# JCM800-2204.net
KiCad netlist of a schematic drawn in Altium Designer
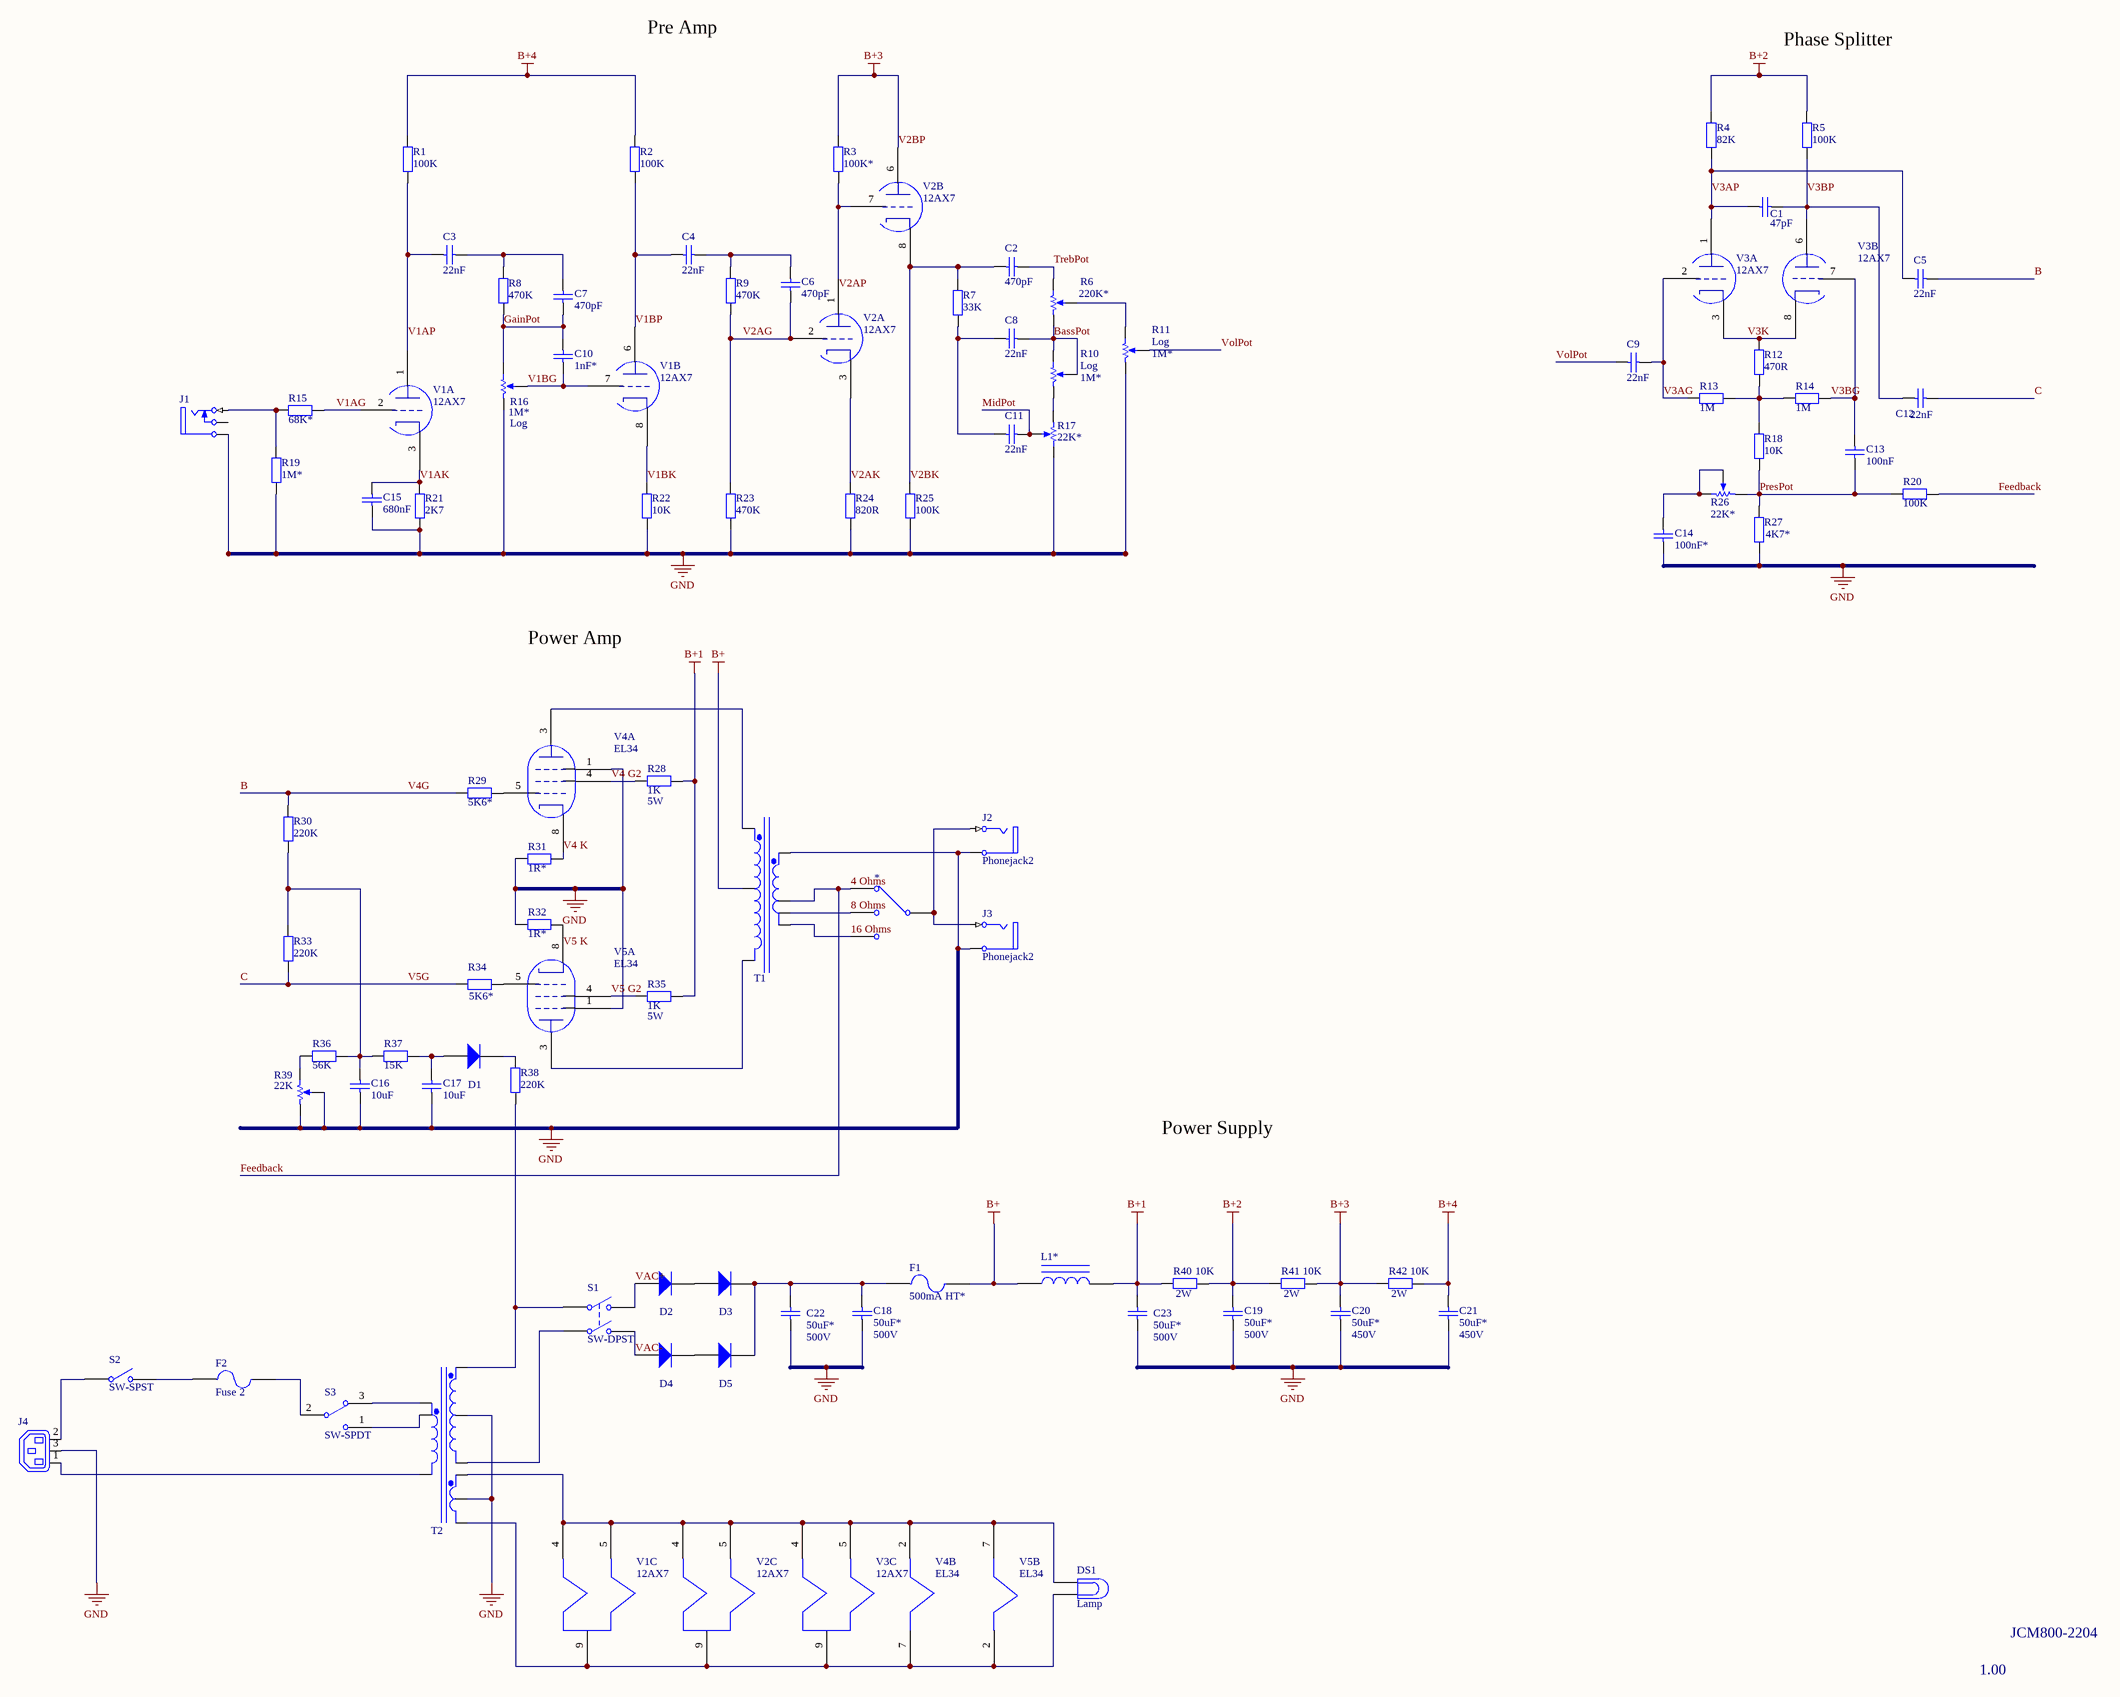
[diagram p0: JCM800-2204.SchDoc]

(export (version "E")
  (design (tool "Eeschema 10.0.6"))
  (components
    (comp (ref "*") (value "Switch 3way") (libsource (lib "RAKS") (part "Switch 3way")))
    (comp (ref "C1")
      (value "47pF")
      (footprint "3CM TURRET")
      (description "Capacitor, ceramic, RSV, 50V, 0805")
      (fields
        (field (name "PART NUMBER") "RK-cer-RSV-50V-0805")
        (field (name "Comment") "Cap-cer-RSV-50V-0805")
      )
      (libsource (lib "RAKS") (part "Cap-cer-RSV-50V-0805"))
    )
    (comp (ref "C2")
      (value "470pF")
      (footprint "6cm Turret")
      (description "Capacitor, ceramic, RSV, 50V, 0805")
      (fields
        (field (name "PART NUMBER") "RK-cer-RSV-50V-0805")
        (field (name "Comment") "Cap-cer-RSV-50V-0805")
      )
      (libsource (lib "RAKS") (part "Cap-cer-RSV-50V-0805"))
    )
    (comp (ref "C3")
      (value "22nF")
      (footprint "3CM TURRET")
      (description "Capacitor, ceramic, RSV, 50V, 0805")
      (fields
        (field (name "PART NUMBER") "RK-cer-RSV-50V-0805")
        (field (name "Comment") "Cap-cer-RSV-50V-0805")
      )
      (libsource (lib "RAKS") (part "Cap-cer-RSV-50V-0805"))
    )
    (comp (ref "C4")
      (value "22nF")
      (footprint "3CM TURRET")
      (description "Capacitor, ceramic, RSV, 50V, 0805")
      (fields
        (field (name "PART NUMBER") "RK-cer-RSV-50V-0805")
        (field (name "Comment") "Cap-cer-RSV-50V-0805")
      )
      (libsource (lib "RAKS") (part "Cap-cer-RSV-50V-0805"))
    )
    (comp (ref "C5")
      (value "22nF")
      (footprint "6CM TURRET")
      (description "Capacitor, ceramic, RSV, 50V, 0805")
      (fields
        (field (name "PART NUMBER") "RK-cer-RSV-50V-0805")
        (field (name "Comment") "Cap-cer-RSV-50V-0805")
      )
      (libsource (lib "RAKS") (part "Cap-cer-RSV-50V-0805"))
    )
    (comp (ref "C6")
      (value "470pF")
      (description "Capacitor, ceramic, RSV, 50V, 0805")
      (fields
        (field (name "PART NUMBER") "RK-cer-RSV-50V-0805")
        (field (name "Comment") "Cap-cer-RSV-50V-0805")
      )
      (libsource (lib "RAKS") (part "Cap-cer-RSV-50V-0805"))
    )
    (comp (ref "C7")
      (value "470pF")
      (description "Capacitor, ceramic, RSV, 50V, 0805")
      (fields
        (field (name "PART NUMBER") "RK-cer-RSV-50V-0805")
        (field (name "Comment") "Cap-cer-RSV-50V-0805")
      )
      (libsource (lib "RAKS") (part "Cap-cer-RSV-50V-0805"))
    )
    (comp (ref "C8")
      (value "22nF")
      (footprint "6cm Turret")
      (description "Capacitor, ceramic, RSV, 50V, 0805")
      (fields
        (field (name "PART NUMBER") "RK-cer-RSV-50V-0805")
        (field (name "Comment") "Cap-cer-RSV-50V-0805")
      )
      (libsource (lib "RAKS") (part "Cap-cer-RSV-50V-0805"))
    )
    (comp (ref "C9")
      (value "22nF")
      (footprint "6cm Turret")
      (description "Capacitor, ceramic, RSV, 50V, 0805")
      (fields
        (field (name "PART NUMBER") "RK-cer-RSV-50V-0805")
        (field (name "Comment") "Cap-cer-RSV-50V-0805")
      )
      (libsource (lib "RAKS") (part "Cap-cer-RSV-50V-0805"))
    )
    (comp (ref "C10")
      (value "1nF*")
      (description "Capacitor, ceramic, RSV, 50V, 0805")
      (fields
        (field (name "PART NUMBER") "RK-cer-RSV-50V-0805")
        (field (name "Comment") "Cap-cer-RSV-50V-0805")
      )
      (libsource (lib "RAKS") (part "Cap-cer-RSV-50V-0805"))
    )
    (comp (ref "C11")
      (value "22nF")
      (footprint "6cm Turret")
      (description "Capacitor, ceramic, RSV, 50V, 0805")
      (fields
        (field (name "PART NUMBER") "RK-cer-RSV-50V-0805")
        (field (name "Comment") "Cap-cer-RSV-50V-0805")
      )
      (libsource (lib "RAKS") (part "Cap-cer-RSV-50V-0805"))
    )
    (comp (ref "C12")
      (value "22nF")
      (footprint "6CM TURRET")
      (description "Capacitor, ceramic, RSV, 50V, 0805")
      (fields
        (field (name "PART NUMBER") "RK-cer-RSV-50V-0805")
        (field (name "Comment") "Cap-cer-RSV-50V-0805")
      )
      (libsource (lib "RAKS") (part "Cap-cer-RSV-50V-0805"))
    )
    (comp (ref "C13")
      (value "100nF")
      (footprint "6CM TURRET")
      (description "Capacitor, ceramic, RSV, 50V, 0805")
      (fields
        (field (name "PART NUMBER") "RK-cer-RSV-50V-0805")
        (field (name "Comment") "Cap-cer-RSV-50V-0805")
      )
      (libsource (lib "RAKS") (part "Cap-cer-RSV-50V-0805"))
    )
    (comp (ref "C14")
      (value "100nF*")
      (description "Capacitor, ceramic, RSV, 50V, 0805")
      (fields
        (field (name "PART NUMBER") "RK-cer-RSV-50V-0805")
        (field (name "Comment") "Cap-cer-RSV-50V-0805")
      )
      (libsource (lib "RAKS") (part "Cap-cer-RSV-50V-0805"))
    )
    (comp (ref "C15")
      (value "680nF")
      (description "Capacitor, ceramic, RSV, 50V, 0805")
      (fields
        (field (name "PART NUMBER") "RK-cer-RSV-50V-0805")
        (field (name "Comment") "Cap-cer-RSV-50V-0805")
      )
      (libsource (lib "RAKS") (part "Cap-cer-RSV-50V-0805"))
    )
    (comp (ref "C16")
      (value "10uF")
      (footprint "6CM TURRET")
      (description "Capacitor, ceramic, RSV, 50V, 0805")
      (fields
        (field (name "PART NUMBER") "RK-cer-RSV-50V-0805")
        (field (name "Comment") "Cap-cer-RSV-50V-0805")
      )
      (libsource (lib "RAKS") (part "Cap-cer-RSV-50V-0805"))
    )
    (comp (ref "C17")
      (value "10uF")
      (footprint "6CM TURRET")
      (description "Capacitor, ceramic, RSV, 50V, 0805")
      (fields
        (field (name "PART NUMBER") "RK-cer-RSV-50V-0805")
        (field (name "Comment") "Cap-cer-RSV-50V-0805")
      )
      (libsource (lib "RAKS") (part "Cap-cer-RSV-50V-0805"))
    )
    (comp (ref "C18")
      (value "50uF*")
      (footprint "6cm Turret")
      (description "Capacitor, ceramic, RSV, 50V, 0805")
      (fields
        (field (name "PART NUMBER") "RK-cer-RSV-50V-0805")
        (field (name "VOLTAGE") "500V")
        (field (name "Comment") "Cap-cer-RSV-50V-0805")
      )
      (libsource (lib "RAKS") (part "Cap-cer-RSV-50V-0805"))
    )
    (comp (ref "C19")
      (value "50uF*")
      (footprint "6cm Turret")
      (description "Capacitor, ceramic, RSV, 50V, 0805")
      (fields
        (field (name "PART NUMBER") "RK-cer-RSV-50V-0805")
        (field (name "VOLTAGE") "500V")
        (field (name "Comment") "Cap-cer-RSV-50V-0805")
      )
      (libsource (lib "RAKS") (part "Cap-cer-RSV-50V-0805"))
    )
    (comp (ref "C20")
      (value "50uF*")
      (footprint "6cm Turret")
      (description "Capacitor, ceramic, RSV, 50V, 0805")
      (fields
        (field (name "PART NUMBER") "RK-cer-RSV-50V-0805")
        (field (name "VOLTAGE") "450V")
        (field (name "Comment") "Cap-cer-RSV-50V-0805")
      )
      (libsource (lib "RAKS") (part "Cap-cer-RSV-50V-0805"))
    )
    (comp (ref "C21")
      (value "50uF*")
      (footprint "6cm Turret")
      (description "Capacitor, ceramic, RSV, 50V, 0805")
      (fields
        (field (name "PART NUMBER") "RK-cer-RSV-50V-0805")
        (field (name "VOLTAGE") "450V")
        (field (name "Comment") "Cap-cer-RSV-50V-0805")
      )
      (libsource (lib "RAKS") (part "Cap-cer-RSV-50V-0805"))
    )
    (comp (ref "C22")
      (value "50uF*")
      (description "Capacitor, ceramic, RSV, 50V, 0805")
      (fields
        (field (name "PART NUMBER") "RK-cer-RSV-50V-0805")
        (field (name "VOLTAGE") "500V")
        (field (name "Comment") "Cap-cer-RSV-50V-0805")
      )
      (libsource (lib "RAKS") (part "Cap-cer-RSV-50V-0805"))
    )
    (comp (ref "C23")
      (value "50uF*")
      (footprint "6cm Turret")
      (description "Capacitor, ceramic, RSV, 50V, 0805")
      (fields
        (field (name "PART NUMBER") "RK-cer-RSV-50V-0805")
        (field (name "VOLTAGE") "500V")
        (field (name "Comment") "Cap-cer-RSV-50V-0805")
      )
      (libsource (lib "RAKS") (part "Cap-cer-RSV-50V-0805"))
    )
    (comp (ref "D1")
      (value "1N4148")
      (footprint "3cm Turret")
      (description "Diode")
      (fields (field (name "PART NUMBER") "RK-Diode-1N4148"))
      (libsource (lib "RAKS") (part "Diode-1N4148"))
    )
    (comp (ref "D2")
      (value "1N4148")
      (footprint "3cm Turret")
      (description "Diode")
      (fields (field (name "PART NUMBER") "RK-Diode-1N4148"))
      (libsource (lib "RAKS") (part "Diode-1N4148"))
    )
    (comp (ref "D3")
      (value "1N4148")
      (footprint "3cm Turret")
      (description "Diode")
      (fields (field (name "PART NUMBER") "RK-Diode-1N4148"))
      (libsource (lib "RAKS") (part "Diode-1N4148"))
    )
    (comp (ref "D4")
      (value "1N4148")
      (footprint "3cm Turret")
      (description "Diode")
      (fields (field (name "PART NUMBER") "RK-Diode-1N4148"))
      (libsource (lib "RAKS") (part "Diode-1N4148"))
    )
    (comp (ref "D5")
      (value "1N4148")
      (footprint "3cm Turret")
      (description "Diode")
      (fields (field (name "PART NUMBER") "RK-Diode-1N4148"))
      (libsource (lib "RAKS") (part "Diode-1N4148"))
    )
    (comp (ref "DS1")
      (value "Lamp")
      (description "Incandescent Bulb")
      (fields (field (name "PUBLISHER") "Altium Limited"))
      (libsource (lib "Miscellaneous Devices") (part "Lamp"))
    )
    (comp (ref "F1")
      (value "500mA HT*")
      (description "Fuse")
      (fields (field (name "PUBLISHER") "Altium Limited"))
      (libsource (lib "Miscellaneous Devices") (part "Fuse 2"))
    )
    (comp (ref "F2")
      (value "Fuse 2")
      (description "Fuse")
      (fields (field (name "PUBLISHER") "Altium Limited"))
      (libsource (lib "Miscellaneous Devices") (part "Fuse 2"))
    )
    (comp (ref "J1")
      (value "Phonejack2 TN")
      (footprint "JACK/6-V3A")
      (description "Jack Socket, 1/4\" [6.5mm], Thru-Hole, Vertical, 2-Conductor with Tip closed")
      (fields (field (name "PUBLISHER") "Altium Limited"))
      (libsource (lib "Miscellaneous Connectors") (part "Phonejack2 TN"))
    )
    (comp (ref "J2")
      (value "Phonejack2")
      (footprint "JACK/6-V2")
      (description "Jack Socket, 1/4\" [6.5mm], Thru-Hole, Vertical, 2-Conductor Open Circuit")
      (fields (field (name "PUBLISHER") "Altium Limited"))
      (libsource (lib "Miscellaneous Connectors") (part "Phonejack2"))
    )
    (comp (ref "J3")
      (value "Phonejack2")
      (footprint "JACK/6-V2")
      (description "Jack Socket, 1/4\" [6.5mm], Thru-Hole, Vertical, 2-Conductor Open Circuit")
      (fields (field (name "PUBLISHER") "Altium Limited"))
      (libsource (lib "Miscellaneous Connectors") (part "Phonejack2"))
    )
    (comp (ref "J4")
      (value "Plug AC Female")
      (description "IEC Mains Power Outlet, EN60 320-2-2 F Class I, PC Flange Rear Mount, Chassis Socket")
      (fields (field (name "PUBLISHER") "Altium Limited"))
      (libsource (lib "Miscellaneous Connectors") (part "Plug AC Female"))
    )
    (comp (ref "L1*")
      (value "Inductor Iron")
      (description "Magnetic-Core Inductor")
      (fields (field (name "PUBLISHER") "Altium Limited"))
      (libsource (lib "Miscellaneous Devices") (part "Inductor Iron"))
    )
    (comp (ref "R1")
      (value "100K")
      (footprint "3CM TURRET")
      (description "Resistor, 100K, 0805, 1%, 1/8W")
      (fields
        (field (name "PART NUMBER") "RK-100K-0805-1%-1/8W")
        (field (name "Comment") "Res-100K-0805-1%-1/8W")
      )
      (libsource (lib "RAKS") (part "Res-100K-0805-1%-1/8W"))
    )
    (comp (ref "R2")
      (value "100K")
      (footprint "3CM TURRET")
      (description "Resistor, 100K, 0805, 1%, 1/8W")
      (fields
        (field (name "PART NUMBER") "RK-100K-0805-1%-1/8W")
        (field (name "Comment") "Res-100K-0805-1%-1/8W")
      )
      (libsource (lib "RAKS") (part "Res-100K-0805-1%-1/8W"))
    )
    (comp (ref "R3")
      (value "100K*")
      (description "Resistor, 100K, 0805, 1%, 1/8W")
      (fields
        (field (name "PART NUMBER") "RK-100K-0805-1%-1/8W")
        (field (name "Comment") "Res-100K-0805-1%-1/8W")
      )
      (libsource (lib "RAKS") (part "Res-100K-0805-1%-1/8W"))
    )
    (comp (ref "R4")
      (value "82K")
      (footprint "3CM TURRET")
      (description "Resistor, 82K, 0805, 1%, 1/8W")
      (fields
        (field (name "PART NUMBER") "RK-82K-0805-1%-1/8W")
        (field (name "Comment") "Res-82K-0805-1%-1/8W")
      )
      (libsource (lib "RAKS") (part "Res-82K-0805-1%-1/8W"))
    )
    (comp (ref "R5")
      (value "100K")
      (footprint "3CM TURRET")
      (description "Resistor, 100K, 0805, 1%, 1/8W")
      (fields
        (field (name "PART NUMBER") "RK-100K-0805-1%-1/8W")
        (field (name "Comment") "Res-100K-0805-1%-1/8W")
      )
      (libsource (lib "RAKS") (part "Res-100K-0805-1%-1/8W"))
    )
    (comp (ref "R6")
      (value "220K*")
      (description "Potentiometer")
      (fields (field (name "Comment") "RPot") (field (name "PUBLISHER") "Altium Limited"))
      (libsource (lib "Miscellaneous Devices") (part "RPot"))
    )
    (comp (ref "R7")
      (value "33K")
      (footprint "3CM TURRET")
      (description "Resistor, 33K, 0805, 1%, 1/8W")
      (fields
        (field (name "PART NUMBER") "RK-33K-0805-1%-1/8W")
        (field (name "Comment") "Res-33K-0805-1%-1/8W")
      )
      (libsource (lib "RAKS") (part "Res-33K-0805-1%-1/8W"))
    )
    (comp (ref "R8")
      (value "470K")
      (footprint "3CM TURRET")
      (description "Resistor, 470K, 0805, 1%, 1/8W")
      (fields
        (field (name "PART NUMBER") "RK-470K-0805-1%-1/8W")
        (field (name "Comment") "Res-470K-0805-1%-1/8W")
      )
      (libsource (lib "RAKS") (part "Res-470K-0805-1%-1/8W"))
    )
    (comp (ref "R9")
      (value "470K")
      (footprint "6CM TURRET")
      (description "Resistor, 470K, 0805, 1%, 1/8W")
      (fields
        (field (name "PART NUMBER") "RK-470K-0805-1%-1/8W")
        (field (name "Comment") "Res-470K-0805-1%-1/8W")
      )
      (libsource (lib "RAKS") (part "Res-470K-0805-1%-1/8W"))
    )
    (comp (ref "R10")
      (value "Log")
      (description "Potentiometer")
      (fields (field (name "ALTIUM_VALUE") "1M*") (field (name "PUBLISHER") "Altium Limited"))
      (libsource (lib "Miscellaneous Devices") (part "RPot"))
    )
    (comp (ref "R11")
      (value "Log")
      (description "Potentiometer")
      (fields (field (name "ALTIUM_VALUE") "1M*") (field (name "PUBLISHER") "Altium Limited"))
      (libsource (lib "Miscellaneous Devices") (part "RPot"))
    )
    (comp (ref "R12")
      (value "470R")
      (footprint "3CM TURRET")
      (description "Resistor, RSV, 0805, 1%, 1/8W")
      (fields
        (field (name "PART NUMBER") "RK-RSV-0805-1%-1/8W")
        (field (name "Comment") "Res-RSV-0805-1%-1/8W")
      )
      (libsource (lib "") (part "Res-RSV-0805-1%-1/8W_1"))
    )
    (comp (ref "R13")
      (value "1M")
      (footprint "3CM TURRET")
      (description "Resistor, 1M, 0805, 1%, 1/8W")
      (fields
        (field (name "PART NUMBER") "RK-1M-0805-1%-1/8W")
        (field (name "Comment") "Res-1M-0805-1%-1/8W")
      )
      (libsource (lib "RAKS") (part "Res-1M-0805-1%-1/8W"))
    )
    (comp (ref "R14")
      (value "1M")
      (footprint "3CM TURRET")
      (description "Resistor, 1M, 0805, 1%, 1/8W")
      (fields
        (field (name "PART NUMBER") "RK-1M-0805-1%-1/8W")
        (field (name "Comment") "Res-1M-0805-1%-1/8W")
      )
      (libsource (lib "RAKS") (part "Res-1M-0805-1%-1/8W"))
    )
    (comp (ref "R15")
      (value "68K*")
      (description "Resistor, 68K, 0805, 1%, 1/8W")
      (fields
        (field (name "PART NUMBER") "RK-68K-0805-1%-1/8W")
        (field (name "Comment") "Res-68K-0805-1%-1/8W")
      )
      (libsource (lib "RAKS") (part "Res-68K-0805-1%-1/8W"))
    )
    (comp (ref "R16")
      (value "Log")
      (description "Potentiometer")
      (fields (field (name "ALTIUM_VALUE") "1M*") (field (name "PUBLISHER") "Altium Limited"))
      (libsource (lib "Miscellaneous Devices") (part "RPot"))
    )
    (comp (ref "R17")
      (value "22K*")
      (description "Potentiometer")
      (fields (field (name "Comment") "RPot") (field (name "PUBLISHER") "Altium Limited"))
      (libsource (lib "Miscellaneous Devices") (part "RPot"))
    )
    (comp (ref "R18")
      (value "10K")
      (footprint "3CM TURRET")
      (description "Resistor, 10K, 0805, 1%, 1/8W")
      (fields
        (field (name "PART NUMBER") "RK-10K-0805-1%-1/8W")
        (field (name "Comment") "Res-10K-0805-1%-1/8W")
      )
      (libsource (lib "RAKS") (part "Res-10K-0805-1%-1/8W"))
    )
    (comp (ref "R19")
      (value "1M*")
      (description "Resistor, 1M, 0805, 1%, 1/8W")
      (fields
        (field (name "PART NUMBER") "RK-1M-0805-1%-1/8W")
        (field (name "Comment") "Res-1M-0805-1%-1/8W")
      )
      (libsource (lib "") (part "Res-1M-0805-1%-1/8W_1"))
    )
    (comp (ref "R20")
      (value "100K")
      (footprint "6CM TURRET")
      (description "Resistor, 100K, 0805, 1%, 1/8W")
      (fields
        (field (name "PART NUMBER") "RK-100K-0805-1%-1/8W")
        (field (name "Comment") "Res-100K-0805-1%-1/8W")
      )
      (libsource (lib "") (part "Res-100K-0805-1%-1/8W_1"))
    )
    (comp (ref "R21")
      (value "2K7")
      (footprint "6CM TURRET")
      (description "Resistor, 2K7, 0805, 1%, 1/8W")
      (fields
        (field (name "PART NUMBER") "RK-2K7-0805-1%-1/8W")
        (field (name "Comment") "Res-2K7-0805-1%-1/8W")
      )
      (libsource (lib "RAKS") (part "Res-2K7-0805-1%-1/8W"))
    )
    (comp (ref "R22")
      (value "10K")
      (footprint "6CM TURRET")
      (description "Resistor, 10K, 0805, 1%, 1/8W")
      (fields
        (field (name "PART NUMBER") "RK-10K-0805-1%-1/8W")
        (field (name "Comment") "Res-10K-0805-1%-1/8W")
      )
      (libsource (lib "RAKS") (part "Res-10K-0805-1%-1/8W"))
    )
    (comp (ref "R23")
      (value "470K")
      (footprint "6CM TURRET")
      (description "Resistor, 470K, 0805, 1%, 1/8W")
      (fields
        (field (name "PART NUMBER") "RK-470K-0805-1%-1/8W")
        (field (name "Comment") "Res-470K-0805-1%-1/8W")
      )
      (libsource (lib "RAKS") (part "Res-470K-0805-1%-1/8W"))
    )
    (comp (ref "R24")
      (value "820R")
      (footprint "6CM TURRET")
      (description "Resistor, 820R, 0805, 1%, 1/8W")
      (fields
        (field (name "PART NUMBER") "RK-820R-0805-1%-1/8W")
        (field (name "Comment") "Res-820R-0805-1%-1/8W")
      )
      (libsource (lib "RAKS") (part "Res-820R-0805-1%-1/8W"))
    )
    (comp (ref "R25")
      (value "100K")
      (footprint "6CM TURRET")
      (description "Resistor, 100K, 0805, 1%, 1/8W")
      (fields
        (field (name "PART NUMBER") "RK-100K-0805-1%-1/8W")
        (field (name "Comment") "Res-100K-0805-1%-1/8W")
      )
      (libsource (lib "RAKS") (part "Res-100K-0805-1%-1/8W"))
    )
    (comp (ref "R26")
      (value "22K*")
      (description "Potentiometer")
      (fields (field (name "Comment") "RPot") (field (name "PUBLISHER") "Altium Limited"))
      (libsource (lib "Miscellaneous Devices") (part "RPot"))
    )
    (comp (ref "R27")
      (value "4K7*")
      (description "Resistor, 4K7, 0805, 1%, 1/8W")
      (fields
        (field (name "PART NUMBER") "RK-4K7-0805-1%-1/8W")
        (field (name "Comment") "Res-4K7-0805-1%-1/8W")
      )
      (libsource (lib "RAKS") (part "Res-4K7-0805-1%-1/8W"))
    )
    (comp (ref "R28")
      (value "1K")
      (footprint "6cm Turret")
      (description "Resistor, 1K, 0805, 1%, 1/8W")
      (fields
        (field (name "PART NUMBER") "RK-1K-0805-1%-1/8W")
        (field (name "WATTS") "5W")
        (field (name "Comment") "Res-1K-0805-1%-1/8W")
      )
      (libsource (lib "RAKS") (part "Res-1K-0805-1%-1/8W"))
    )
    (comp (ref "R29")
      (value "5K6*")
      (description "Resistor, 5K6, 0805, 1%, 1/8W")
      (fields
        (field (name "PART NUMBER") "RK-5K6-0805-1%-1/8W")
        (field (name "Comment") "Res-5K6-0805-1%-1/8W")
      )
      (libsource (lib "RAKS") (part "Res-5K6-0805-1%-1/8W"))
    )
    (comp (ref "R30")
      (value "220K")
      (footprint "3CM TURRET")
      (description "Resistor, 150K, 0805, 1%, 1/8W")
      (fields
        (field (name "PART NUMBER") "RK-150K-0805-1%-1/8W")
        (field (name "Comment") "Res-150K-0805-1%-1/8W")
      )
      (libsource (lib "RAKS") (part "Res-150K-0805-1%-1/8W"))
    )
    (comp (ref "R31")
      (value "1R*")
      (description "Resistor, RSV, 0805, 1%, 1/8W")
      (fields
        (field (name "PART NUMBER") "RK-RSV-0805-1%-1/8W")
        (field (name "Comment") "Res-RSV-0805-1%-1/8W")
      )
      (libsource (lib "RAKS") (part "Res-RSV-0805-1%-1/8W"))
    )
    (comp (ref "R32")
      (value "1R*")
      (description "Resistor, RSV, 0805, 1%, 1/8W")
      (fields
        (field (name "PART NUMBER") "RK-RSV-0805-1%-1/8W")
        (field (name "Comment") "Res-RSV-0805-1%-1/8W")
      )
      (libsource (lib "RAKS") (part "Res-RSV-0805-1%-1/8W"))
    )
    (comp (ref "R33")
      (value "220K")
      (footprint "3CM TURRET")
      (description "Resistor, 150K, 0805, 1%, 1/8W")
      (fields
        (field (name "PART NUMBER") "RK-150K-0805-1%-1/8W")
        (field (name "Comment") "Res-150K-0805-1%-1/8W")
      )
      (libsource (lib "RAKS") (part "Res-150K-0805-1%-1/8W"))
    )
    (comp (ref "R34")
      (value "5K6*")
      (description "Resistor, 5K6, 0805, 1%, 1/8W")
      (fields
        (field (name "PART NUMBER") "RK-5K6-0805-1%-1/8W")
        (field (name "Comment") "Res-5K6-0805-1%-1/8W")
      )
      (libsource (lib "RAKS") (part "Res-5K6-0805-1%-1/8W"))
    )
    (comp (ref "R35")
      (value "1K")
      (footprint "6cm Turret")
      (description "Resistor, 1K, 0805, 1%, 1/8W")
      (fields
        (field (name "PART NUMBER") "RK-1K-0805-1%-1/8W")
        (field (name "WATTS") "5W")
        (field (name "Comment") "Res-1K-0805-1%-1/8W")
      )
      (libsource (lib "RAKS") (part "Res-1K-0805-1%-1/8W"))
    )
    (comp (ref "R36")
      (value "56K")
      (footprint "3CM TURRET")
      (description "Resistor, 47K, 0805, 1%, 1/8W")
      (fields
        (field (name "PART NUMBER") "RK-47K-0805-1%-1/8W")
        (field (name "Comment") "Res-47K-0805-1%-1/8W")
      )
      (libsource (lib "RAKS") (part "Res-47K-0805-1%-1/8W"))
    )
    (comp (ref "R37")
      (value "15K")
      (footprint "3CM TURRET")
      (description "Resistor, 15K, 0805, 1%, 1/8W")
      (fields
        (field (name "PART NUMBER") "RK-15K-0805-1%-1/8W")
        (field (name "Comment") "Res-15K-0805-1%-1/8W")
      )
      (libsource (lib "RAKS") (part "Res-15K-0805-1%-1/8W"))
    )
    (comp (ref "R38")
      (value "220K")
      (footprint "3CM TURRET")
      (description "Resistor, 120K, 0805, 1%, 1/8W")
      (fields
        (field (name "PART NUMBER") "RK-120K-0805-1%-1/8W")
        (field (name "Comment") "Res-120K-0805-1%-1/8W")
      )
      (libsource (lib "RAKS") (part "Res-120K-0805-1%-1/8W"))
    )
    (comp (ref "R39")
      (value "22K")
      (footprint "VR5")
      (description "Potentiometer")
      (fields (field (name "Comment") "RPot") (field (name "PUBLISHER") "Altium Limited"))
      (libsource (lib "Miscellaneous Devices") (part "RPot"))
    )
    (comp (ref "R40")
      (value "10K")
      (footprint "3cm Turret")
      (description "Resistor, 10K, 0805, 1%, 1/8W")
      (fields
        (field (name "PART NUMBER") "RK-10K-0805-1%-1/8W")
        (field (name "WATTS") "2W")
        (field (name "Comment") "Res-10K-0805-1%-1/8W")
      )
      (libsource (lib "") (part "Res-10K-0805-1%-1/8W_1"))
    )
    (comp (ref "R41")
      (value "10K")
      (footprint "3cm Turret")
      (description "Resistor, 10K, 0805, 1%, 1/8W")
      (fields
        (field (name "PART NUMBER") "RK-10K-0805-1%-1/8W")
        (field (name "WATTS") "2W")
        (field (name "Comment") "Res-10K-0805-1%-1/8W")
      )
      (libsource (lib "") (part "Res-10K-0805-1%-1/8W_1"))
    )
    (comp (ref "R42")
      (value "10K")
      (footprint "3cm Turret")
      (description "Resistor, 10K, 0805, 1%, 1/8W")
      (fields
        (field (name "PART NUMBER") "RK-10K-0805-1%-1/8W")
        (field (name "WATTS") "2W")
        (field (name "Comment") "Res-10K-0805-1%-1/8W")
      )
      (libsource (lib "") (part "Res-10K-0805-1%-1/8W_1"))
    )
    (comp (ref "S1")
      (value "SW-DPST")
      (description "Double-Pole, Single-Throw Switch")
      (fields (field (name "PUBLISHER") "Altium Limited"))
      (libsource (lib "Miscellaneous Devices") (part "SW-DPST"))
    )
    (comp (ref "S2")
      (value "SW-SPST")
      (description "Single-Pole, Single-Throw Switch")
      (fields (field (name "PUBLISHER") "Altium Limited"))
      (libsource (lib "Miscellaneous Devices") (part "SW-SPST"))
    )
    (comp (ref "S3")
      (value "SW-SPDT")
      (description "SPDT Subminiature Toggle Switch, Right Angle Mounting, Vertical Actuation")
      (fields (field (name "PUBLISHER") "Altium Limited"))
      (libsource (lib "Miscellaneous Devices") (part "SW-SPDT"))
    )
    (comp (ref "T1") (value "Transformador Saida") (libsource (lib "RAKS") (part "Transformador Saida")))
    (comp (ref "T2") (value "Transformer") (libsource (lib "RAKS") (part "Transformer")))
    (comp (ref "V1") (value "12AX7") (description "Tube") (libsource (lib "RAKS") (part "12AX7")))
    (comp (ref "V2") (value "12AX7") (description "Tube") (libsource (lib "RAKS") (part "12AX7")))
    (comp (ref "V3") (value "12AX7") (description "Tube") (libsource (lib "RAKS") (part "12AX7")))
    (comp (ref "V4") (value "EL34") (libsource (lib "") (part "EL34_1")))
    (comp (ref "V5") (value "EL34") (libsource (lib "RAKS") (part "EL34")))
  )
  (nets
    (net (code "1") (name "/4 Ohms") (class "Default")
      (node (ref "*") (pin "1") (pinfunction "1_1") (pintype "passive"))
      (node (ref "R20") (pin "1") (pinfunction "1_1") (pintype "passive"))
      (node (ref "T1") (pin "6") (pinfunction "Sec2-_6") (pintype "passive"))
    )
    (net (code "2") (name "/8 Ohms") (class "Default")
      (node (ref "*") (pin "3") (pinfunction "3_3") (pintype "passive"))
      (node (ref "T1") (pin "5") (pinfunction "Sec2+_5") (pintype "passive"))
    )
    (net (code "3") (name "/16 Ohms") (class "Default")
      (node (ref "*") (pin "1") (pinfunction "1_1") (pintype "passive"))
      (node (ref "T1") (pin "4") (pinfunction "Sec1-_4") (pintype "passive"))
    )
    (net (code "4") (name "/B") (class "Default")
      (node (ref "C5") (pin "1") (pinfunction "1_1") (pintype "passive"))
      (node (ref "R29") (pin "1") (pinfunction "1_1") (pintype "passive"))
      (node (ref "R30") (pin "2") (pinfunction "2_2") (pintype "passive"))
    )
    (net (code "5") (name "/BassPot") (class "Default")
      (node (ref "C8") (pin "1") (pinfunction "1_1") (pintype "passive"))
      (node (ref "R10") (pin "1") (pinfunction "TOP_1") (pintype "passive"))
      (node (ref "R10") (pin "3") (pinfunction "TAP_3") (pintype "passive"))
      (node (ref "R6") (pin "2") (pinfunction "BOT_2") (pintype "passive"))
    )
    (net (code "6") (name "/C") (class "Default")
      (node (ref "C12") (pin "1") (pinfunction "1_1") (pintype "passive"))
      (node (ref "R33") (pin "1") (pinfunction "1_1") (pintype "passive"))
      (node (ref "R34") (pin "1") (pinfunction "1_1") (pintype "passive"))
    )
    (net (code "7") (name "/GainPot") (class "Default")
      (node (ref "C10") (pin "1") (pinfunction "1_1") (pintype "passive"))
      (node (ref "C7") (pin "2") (pinfunction "2_2") (pintype "passive"))
      (node (ref "R16") (pin "1") (pinfunction "TOP_1") (pintype "passive"))
      (node (ref "R8") (pin "1") (pinfunction "1_1") (pintype "passive"))
    )
    (net (code "8") (name "/MidPot") (class "Default")
      (node (ref "C11") (pin "1") (pinfunction "1_1") (pintype "passive"))
      (node (ref "R17") (pin "3") (pinfunction "TAP_3") (pintype "passive"))
    )
    (net (code "9") (name "/PresPot") (class "Default")
      (node (ref "C13") (pin "2") (pinfunction "2_2") (pintype "passive"))
      (node (ref "R18") (pin "1") (pinfunction "1_1") (pintype "passive"))
      (node (ref "R20") (pin "2") (pinfunction "2_2") (pintype "passive"))
      (node (ref "R26") (pin "2") (pinfunction "BOT_2") (pintype "passive"))
      (node (ref "R27") (pin "2") (pinfunction "2_2") (pintype "passive"))
    )
    (net (code "10") (name "/TrebPot") (class "Default")
      (node (ref "C2") (pin "1") (pinfunction "1_1") (pintype "passive"))
      (node (ref "R6") (pin "1") (pinfunction "TOP_1") (pintype "passive"))
    )
    (net (code "11") (name "/V1AG") (class "Default")
      (node (ref "R15") (pin "2") (pinfunction "2_2") (pintype "passive"))
      (node (ref "V1") (pin "2") (pinfunction "Grid_2") (pintype "passive"))
    )
    (net (code "12") (name "/V1AK") (class "Default")
      (node (ref "C15") (pin "2") (pinfunction "2_2") (pintype "passive"))
      (node (ref "R21") (pin "2") (pinfunction "2_2") (pintype "passive"))
      (node (ref "V1") (pin "3") (pinfunction "Cathode_3") (pintype "passive"))
    )
    (net (code "13") (name "/V1AP") (class "Default")
      (node (ref "C3") (pin "2") (pinfunction "2_2") (pintype "passive"))
      (node (ref "R1") (pin "1") (pinfunction "1_1") (pintype "passive"))
      (node (ref "V1") (pin "1") (pinfunction "Plate_1") (pintype "passive"))
    )
    (net (code "14") (name "/V1BG") (class "Default")
      (node (ref "C10") (pin "2") (pinfunction "2_2") (pintype "passive"))
      (node (ref "R16") (pin "3") (pinfunction "TAP_3") (pintype "passive"))
      (node (ref "V1") (pin "7") (pinfunction "Grid_7") (pintype "passive"))
    )
    (net (code "15") (name "/V1BK") (class "Default")
      (node (ref "R22") (pin "2") (pinfunction "2_2") (pintype "passive"))
      (node (ref "V1") (pin "8") (pinfunction "Cathode_8") (pintype "passive"))
    )
    (net (code "16") (name "/V1BP") (class "Default")
      (node (ref "C4") (pin "1") (pinfunction "1_1") (pintype "passive"))
      (node (ref "R2") (pin "1") (pinfunction "1_1") (pintype "passive"))
      (node (ref "V1") (pin "6") (pinfunction "Plate_6") (pintype "passive"))
    )
    (net (code "17") (name "/V2AG") (class "Default")
      (node (ref "C6") (pin "1") (pinfunction "1_1") (pintype "passive"))
      (node (ref "R23") (pin "2") (pinfunction "2_2") (pintype "passive"))
      (node (ref "R9") (pin "1") (pinfunction "1_1") (pintype "passive"))
      (node (ref "V2") (pin "2") (pinfunction "Grid_2") (pintype "passive"))
    )
    (net (code "18") (name "/V2AK") (class "Default")
      (node (ref "R24") (pin "2") (pinfunction "2_2") (pintype "passive"))
      (node (ref "V2") (pin "3") (pinfunction "Cathode_3") (pintype "passive"))
    )
    (net (code "20") (name "/V2BK") (class "Default")
      (node (ref "C2") (pin "2") (pinfunction "2_2") (pintype "passive"))
      (node (ref "R25") (pin "2") (pinfunction "2_2") (pintype "passive"))
      (node (ref "R7") (pin "2") (pinfunction "2_2") (pintype "passive"))
      (node (ref "V2") (pin "8") (pinfunction "Cathode_8") (pintype "passive"))
    )
    (net (code "21") (name "/V3AG") (class "Default")
      (node (ref "C9") (pin "1") (pinfunction "1_1") (pintype "passive"))
      (node (ref "R13") (pin "2") (pinfunction "2_2") (pintype "passive"))
      (node (ref "V3") (pin "2") (pinfunction "Grid_2") (pintype "passive"))
    )
    (net (code "22") (name "/V3AP") (class "Default")
      (node (ref "C1") (pin "2") (pinfunction "2_2") (pintype "passive"))
      (node (ref "C5") (pin "2") (pinfunction "2_2") (pintype "passive"))
      (node (ref "R4") (pin "1") (pinfunction "1_1") (pintype "passive"))
      (node (ref "V3") (pin "1") (pinfunction "Plate_1") (pintype "passive"))
    )
    (net (code "23") (name "/V3BG") (class "Default")
      (node (ref "C13") (pin "1") (pinfunction "1_1") (pintype "passive"))
      (node (ref "R14") (pin "1") (pinfunction "1_1") (pintype "passive"))
      (node (ref "V3") (pin "7") (pinfunction "Grid_7") (pintype "passive"))
    )
    (net (code "24") (name "/V3BP") (class "Default")
      (node (ref "C1") (pin "1") (pinfunction "1_1") (pintype "passive"))
      (node (ref "C12") (pin "2") (pinfunction "2_2") (pintype "passive"))
      (node (ref "R5") (pin "1") (pinfunction "1_1") (pintype "passive"))
      (node (ref "V3") (pin "6") (pinfunction "Plate_6") (pintype "passive"))
    )
    (net (code "25") (name "/V3K") (class "Default")
      (node (ref "R12") (pin "2") (pinfunction "2_2") (pintype "passive"))
      (node (ref "V3") (pin "3") (pinfunction "Cathode_3") (pintype "passive"))
      (node (ref "V3") (pin "8") (pinfunction "Cathode_8") (pintype "passive"))
    )
    (net (code "26") (name "/V4 G2") (class "Default")
      (node (ref "R28") (pin "1") (pinfunction "1_1") (pintype "passive"))
      (node (ref "V4") (pin "4") (pinfunction "g2_4") (pintype "passive"))
    )
    (net (code "27") (name "/V4 K") (class "Default")
      (node (ref "R31") (pin "1") (pinfunction "1_1") (pintype "passive"))
      (node (ref "V4") (pin "8") (pinfunction "Cathode_8") (pintype "passive"))
    )
    (net (code "28") (name "/V5 G2") (class "Default")
      (node (ref "R35") (pin "1") (pinfunction "1_1") (pintype "passive"))
      (node (ref "V5") (pin "4") (pinfunction "g2_4") (pintype "passive"))
    )
    (net (code "30") (name "/VAC+") (class "Default")
      (node (ref "D2") (pin "1") (pinfunction "A_1") (pintype "passive"))
      (node (ref "S1") (pin "2") (pinfunction "NO1_2") (pintype "passive"))
    )
    (net (code "31") (name "/VAC-") (class "Default")
      (node (ref "D4") (pin "1") (pinfunction "A_1") (pintype "passive"))
      (node (ref "S1") (pin "4") (pinfunction "NO2_4") (pintype "passive"))
    )
    (net (code "32") (name "/VolPot") (class "Default")
      (node (ref "C9") (pin "2") (pinfunction "2_2") (pintype "passive"))
      (node (ref "R11") (pin "3") (pinfunction "TAP_3") (pintype "passive"))
    )
    (net (code "33") (name "B+") (class "Default")
      (node (ref "F1") (pin "2") (pinfunction "2_2") (pintype "passive"))
      (node (ref "L1*") (pin "1") (pinfunction "1_1") (pintype "passive"))
      (node (ref "T1") (pin "2") (pinfunction "Pri-_2") (pintype "passive"))
    )
    (net (code "34") (name "B+1") (class "Default")
      (node (ref "C23") (pin "1") (pinfunction "1_1") (pintype "passive"))
      (node (ref "L1*") (pin "2") (pinfunction "2_2") (pintype "passive"))
      (node (ref "R28") (pin "2") (pinfunction "2_2") (pintype "passive"))
      (node (ref "R35") (pin "2") (pinfunction "2_2") (pintype "passive"))
      (node (ref "R40") (pin "2") (pinfunction "2_2") (pintype "passive"))
    )
    (net (code "35") (name "B+2") (class "Default")
      (node (ref "C19") (pin "1") (pinfunction "1_1") (pintype "passive"))
      (node (ref "R4") (pin "2") (pinfunction "2_2") (pintype "passive"))
      (node (ref "R40") (pin "1") (pinfunction "1_1") (pintype "passive"))
      (node (ref "R41") (pin "2") (pinfunction "2_2") (pintype "passive"))
      (node (ref "R5") (pin "2") (pinfunction "2_2") (pintype "passive"))
    )
    (net (code "36") (name "B+3") (class "Default")
      (node (ref "C20") (pin "1") (pinfunction "1_1") (pintype "passive"))
      (node (ref "R3") (pin "2") (pinfunction "2_2") (pintype "passive"))
      (node (ref "R41") (pin "1") (pinfunction "1_1") (pintype "passive"))
      (node (ref "R42") (pin "2") (pinfunction "2_2") (pintype "passive"))
      (node (ref "V2") (pin "6") (pinfunction "Plate_6") (pintype "passive"))
    )
    (net (code "37") (name "B+4") (class "Default")
      (node (ref "C21") (pin "1") (pinfunction "1_1") (pintype "passive"))
      (node (ref "R1") (pin "2") (pinfunction "2_2") (pintype "passive"))
      (node (ref "R2") (pin "2") (pinfunction "2_2") (pintype "passive"))
      (node (ref "R42") (pin "1") (pinfunction "1_1") (pintype "passive"))
    )
    (net (code "38") (name "GND") (class "Default")
      (node (ref "C14") (pin "1") (pinfunction "1_1") (pintype "passive"))
      (node (ref "C15") (pin "1") (pinfunction "1_1") (pintype "passive"))
      (node (ref "C16") (pin "2") (pinfunction "2_2") (pintype "passive"))
      (node (ref "C17") (pin "2") (pinfunction "2_2") (pintype "passive"))
      (node (ref "C18") (pin "2") (pinfunction "2_2") (pintype "passive"))
      (node (ref "C19") (pin "2") (pinfunction "2_2") (pintype "passive"))
      (node (ref "C20") (pin "2") (pinfunction "2_2") (pintype "passive"))
      (node (ref "C21") (pin "2") (pinfunction "2_2") (pintype "passive"))
      (node (ref "C22") (pin "2") (pinfunction "2_2") (pintype "passive"))
      (node (ref "C23") (pin "2") (pinfunction "2_2") (pintype "passive"))
      (node (ref "J1") (pin "5") (pinfunction "S_5") (pintype "power_in"))
      (node (ref "J2") (pin "5") (pinfunction "S_5") (pintype "power_in"))
      (node (ref "J3") (pin "5") (pinfunction "S_5") (pintype "power_in"))
      (node (ref "J4") (pin "3") (pinfunction "E_3") (pintype "power_in"))
      (node (ref "R11") (pin "2") (pinfunction "BOT_2") (pintype "passive"))
      (node (ref "R16") (pin "2") (pinfunction "BOT_2") (pintype "passive"))
      (node (ref "R17") (pin "1") (pinfunction "TOP_1") (pintype "passive"))
      (node (ref "R19") (pin "1") (pinfunction "1_1") (pintype "passive"))
      (node (ref "R21") (pin "1") (pinfunction "1_1") (pintype "passive"))
      (node (ref "R22") (pin "1") (pinfunction "1_1") (pintype "passive"))
      (node (ref "R23") (pin "1") (pinfunction "1_1") (pintype "passive"))
      (node (ref "R24") (pin "1") (pinfunction "1_1") (pintype "passive"))
      (node (ref "R25") (pin "1") (pinfunction "1_1") (pintype "passive"))
      (node (ref "R27") (pin "1") (pinfunction "1_1") (pintype "passive"))
      (node (ref "R31") (pin "2") (pinfunction "2_2") (pintype "passive"))
      (node (ref "R32") (pin "2") (pinfunction "2_2") (pintype "passive"))
      (node (ref "R39") (pin "2") (pinfunction "BOT_2") (pintype "passive"))
      (node (ref "R39") (pin "3") (pinfunction "TAP_3") (pintype "passive"))
      (node (ref "T1") (pin "3") (pinfunction "Sec1+_3") (pintype "passive"))
      (node (ref "T2") (pin "7") (pinfunction "7_7") (pintype "passive"))
      (node (ref "T2") (pin "8") (pinfunction "8_8") (pintype "passive"))
      (node (ref "V4") (pin "1") (pinfunction "g3_1") (pintype "passive"))
      (node (ref "V5") (pin "1") (pinfunction "g3_1") (pintype "passive"))
    )
    (net (code "39") (name "Net-(C3-Pad1)") (class "Default")
      (node (ref "C3") (pin "1") (pinfunction "1_1") (pintype "passive"))
      (node (ref "C7") (pin "1") (pinfunction "1_1") (pintype "passive"))
      (node (ref "R8") (pin "2") (pinfunction "2_2") (pintype "passive"))
    )
    (net (code "40") (name "Net-(C4-Pad2)") (class "Default")
      (node (ref "C4") (pin "2") (pinfunction "2_2") (pintype "passive"))
      (node (ref "C6") (pin "2") (pinfunction "2_2") (pintype "passive"))
      (node (ref "R9") (pin "2") (pinfunction "2_2") (pintype "passive"))
    )
    (net (code "41") (name "Net-(C11-Pad2)") (class "Default")
      (node (ref "C11") (pin "2") (pinfunction "2_2") (pintype "passive"))
      (node (ref "C8") (pin "2") (pinfunction "2_2") (pintype "passive"))
      (node (ref "R7") (pin "1") (pinfunction "1_1") (pintype "passive"))
    )
    (net (code "42") (name "Net-(C16-Pad1)") (class "Default")
      (node (ref "C16") (pin "1") (pinfunction "1_1") (pintype "passive"))
      (node (ref "R30") (pin "1") (pinfunction "1_1") (pintype "passive"))
      (node (ref "R33") (pin "2") (pinfunction "2_2") (pintype "passive"))
      (node (ref "R36") (pin "2") (pinfunction "2_2") (pintype "passive"))
      (node (ref "R37") (pin "1") (pinfunction "1_1") (pintype "passive"))
    )
    (net (code "43") (name "Net-(D1-A)") (class "Default")
      (node (ref "C17") (pin "1") (pinfunction "1_1") (pintype "passive"))
      (node (ref "D1") (pin "1") (pinfunction "A_1") (pintype "passive"))
      (node (ref "R37") (pin "2") (pinfunction "2_2") (pintype "passive"))
    )
    (net (code "44") (name "Net-(D1-K)") (class "Default")
      (node (ref "D1") (pin "2") (pinfunction "K_2") (pintype "passive"))
      (node (ref "R38") (pin "2") (pinfunction "2_2") (pintype "passive"))
    )
    (net (code "45") (name "Net-(D2-K)") (class "Default")
      (node (ref "D2") (pin "2") (pinfunction "K_2") (pintype "passive"))
      (node (ref "D3") (pin "1") (pinfunction "A_1") (pintype "passive"))
    )
    (net (code "46") (name "Net-(D3-K)") (class "Default")
      (node (ref "C18") (pin "1") (pinfunction "1_1") (pintype "passive"))
      (node (ref "C22") (pin "1") (pinfunction "1_1") (pintype "passive"))
      (node (ref "D3") (pin "2") (pinfunction "K_2") (pintype "passive"))
      (node (ref "D5") (pin "2") (pinfunction "K_2") (pintype "passive"))
      (node (ref "F1") (pin "1") (pinfunction "1_1") (pintype "passive"))
    )
    (net (code "47") (name "Net-(D4-K)") (class "Default")
      (node (ref "D4") (pin "2") (pinfunction "K_2") (pintype "passive"))
      (node (ref "D5") (pin "1") (pinfunction "A_1") (pintype "passive"))
    )
    (net (code "48") (name "Net-(F2-Pad2)") (class "Default")
      (node (ref "F2") (pin "2") (pinfunction "2_2") (pintype "passive"))
      (node (ref "S3") (pin "2") (pinfunction "2_2") (pintype "passive"))
    )
    (net (code "49") (name "Net-(J1-T)") (class "Default")
      (node (ref "J1") (pin "1") (pinfunction "T_1") (pintype "input"))
      (node (ref "R15") (pin "1") (pinfunction "1_1") (pintype "passive"))
      (node (ref "R19") (pin "2") (pinfunction "2_2") (pintype "passive"))
    )
    (net (code "50") (name "Net-(J2-T)") (class "Default")
      (node (ref "*") (pin "2") (pinfunction "2_2") (pintype "passive"))
      (node (ref "J2") (pin "1") (pinfunction "T_1") (pintype "input"))
      (node (ref "J3") (pin "1") (pinfunction "T_1") (pintype "input"))
    )
    (net (code "51") (name "Net-(J4-L)") (class "Default")
      (node (ref "J4") (pin "1") (pinfunction "L_1") (pintype "power_in"))
      (node (ref "T2") (pin "2") (pinfunction "Pri-_2") (pintype "passive"))
    )
    (net (code "52") (name "Net-(J4-N)") (class "Default")
      (node (ref "J4") (pin "2") (pinfunction "N_2") (pintype "power_in"))
      (node (ref "S2") (pin "1") (pinfunction "COMMON_1") (pintype "passive"))
    )
    (net (code "53") (name "Net-(R10-BOT)") (class "Default")
      (node (ref "R10") (pin "2") (pinfunction "BOT_2") (pintype "passive"))
      (node (ref "R17") (pin "2") (pinfunction "BOT_2") (pintype "passive"))
    )
    (net (code "54") (name "Net-(R11-TOP)") (class "Default")
      (node (ref "R11") (pin "1") (pinfunction "TOP_1") (pintype "passive"))
      (node (ref "R6") (pin "3") (pinfunction "TAP_3") (pintype "passive"))
    )
    (net (code "55") (name "Net-(R12-Pad1)") (class "Default")
      (node (ref "R12") (pin "1") (pinfunction "1_1") (pintype "passive"))
      (node (ref "R13") (pin "1") (pinfunction "1_1") (pintype "passive"))
      (node (ref "R14") (pin "2") (pinfunction "2_2") (pintype "passive"))
      (node (ref "R18") (pin "2") (pinfunction "2_2") (pintype "passive"))
    )
    (net (code "56") (name "Net-(R26-TAP)") (class "Default")
      (node (ref "C14") (pin "2") (pinfunction "2_2") (pintype "passive"))
      (node (ref "R26") (pin "1") (pinfunction "TOP_1") (pintype "passive"))
      (node (ref "R26") (pin "3") (pinfunction "TAP_3") (pintype "passive"))
    )
    (net (code "57") (name "Net-(R39-TOP)") (class "Default")
      (node (ref "R36") (pin "1") (pinfunction "1_1") (pintype "passive"))
      (node (ref "R39") (pin "1") (pinfunction "TOP_1") (pintype "passive"))
    )
    (net (code "58") (name "Net-(S1-COMMON1)") (class "Default")
      (node (ref "R38") (pin "1") (pinfunction "1_1") (pintype "passive"))
      (node (ref "S1") (pin "1") (pinfunction "COMMON1_1") (pintype "passive"))
      (node (ref "T2") (pin "3") (pinfunction "Sec1+_3") (pintype "passive"))
    )
    (net (code "59") (name "Net-(S1-COMMON2)") (class "Default")
      (node (ref "S1") (pin "3") (pinfunction "COMMON2_3") (pintype "passive"))
      (node (ref "T2") (pin "4") (pinfunction "Sec1-_4") (pintype "passive"))
    )
    (net (code "60") (name "Net-(S2-NO)") (class "Default")
      (node (ref "F2") (pin "1") (pinfunction "1_1") (pintype "passive"))
      (node (ref "S2") (pin "2") (pinfunction "NO_2") (pintype "passive"))
    )
    (net (code "61") (name "Net-(T1-Pri+)") (class "Default")
      (node (ref "T1") (pin "1") (pinfunction "Pri+_1") (pintype "passive"))
      (node (ref "V4") (pin "3") (pinfunction "Plate_3") (pintype "passive"))
    )
    (net (code "62") (name "Net-(T1-Pri-)") (class "Default")
      (node (ref "T1") (pin "2") (pinfunction "Pri-_2") (pintype "passive"))
      (node (ref "V5") (pin "3") (pinfunction "Plate_3") (pintype "passive"))
    )
    (net (code "63") (name "Net-(T2-Pri+)") (class "Default")
      (node (ref "S3") (pin "1") (pinfunction "1_1") (pintype "passive"))
      (node (ref "T2") (pin "1") (pinfunction "Pri+_1") (pintype "passive"))
    )
    (net (code "64") (name "Net-(T2-Pri+)_1") (class "Default")
      (node (ref "S3") (pin "3") (pinfunction "3_3") (pintype "passive"))
      (node (ref "T2") (pin "1") (pinfunction "Pri+_1") (pintype "passive"))
    )
    (net (code "65") (name "Net-(T2-Sec2+)") (class "Default")
      (node (ref "DS1") (pin "1") (pinfunction "1_1") (pintype "passive"))
      (node (ref "T2") (pin "5") (pinfunction "Sec2+_5") (pintype "passive"))
      (node (ref "V1") (pin "4") (pinfunction "4_4") (pintype "passive"))
      (node (ref "V1") (pin "5") (pinfunction "5_5") (pintype "passive"))
      (node (ref "V2") (pin "4") (pinfunction "4_4") (pintype "passive"))
      (node (ref "V2") (pin "5") (pinfunction "5_5") (pintype "passive"))
      (node (ref "V3") (pin "4") (pinfunction "4_4") (pintype "passive"))
      (node (ref "V3") (pin "5") (pinfunction "5_5") (pintype "passive"))
      (node (ref "V4") (pin "2") (pinfunction "2_2") (pintype "passive"))
      (node (ref "V5") (pin "7") (pinfunction "7_7") (pintype "passive"))
    )
    (net (code "66") (name "Net-(T2-Sec2-)") (class "Default")
      (node (ref "DS1") (pin "2") (pinfunction "2_2") (pintype "passive"))
      (node (ref "T2") (pin "6") (pinfunction "Sec2-_6") (pintype "passive"))
      (node (ref "V1") (pin "9") (pinfunction "9_9") (pintype "passive"))
      (node (ref "V2") (pin "9") (pinfunction "9_9") (pintype "passive"))
      (node (ref "V3") (pin "9") (pinfunction "9_9") (pintype "passive"))
      (node (ref "V4") (pin "7") (pinfunction "7_7") (pintype "passive"))
      (node (ref "V5") (pin "2") (pinfunction "2_2") (pintype "passive"))
    )
    (net (code "67") (name "Net-(V2A-Plate)") (class "Default")
      (node (ref "R3") (pin "1") (pinfunction "1_1") (pintype "passive"))
      (node (ref "V2") (pin "1") (pinfunction "Plate_1") (pintype "passive"))
      (node (ref "V2") (pin "7") (pinfunction "Grid_7") (pintype "passive"))
    )
    (net (code "68") (name "Net-(V4A-g1)") (class "Default")
      (node (ref "R29") (pin "2") (pinfunction "2_2") (pintype "passive"))
      (node (ref "V4") (pin "5") (pinfunction "g1_5") (pintype "passive"))
    )
    (net (code "69") (name "Net-(V5A-Cathode)") (class "Default")
      (node (ref "R32") (pin "1") (pinfunction "1_1") (pintype "passive"))
      (node (ref "V5") (pin "8") (pinfunction "Cathode_8") (pintype "passive"))
    )
    (net (code "70") (name "Net-(V5A-g1)") (class "Default")
      (node (ref "R34") (pin "2") (pinfunction "2_2") (pintype "passive"))
      (node (ref "V5") (pin "5") (pinfunction "g1_5") (pintype "passive"))
    )
    (net (code "71") (name "unconnected-(J1-TN-Pad2)") (class "Default")
      (node (ref "J1") (pin "2") (pinfunction "TN_2") (pintype "passive"))
    )
  )
)
